# CHIBI_AMP_20181126.net
KiCad netlist of a schematic drawn in Altium Designer
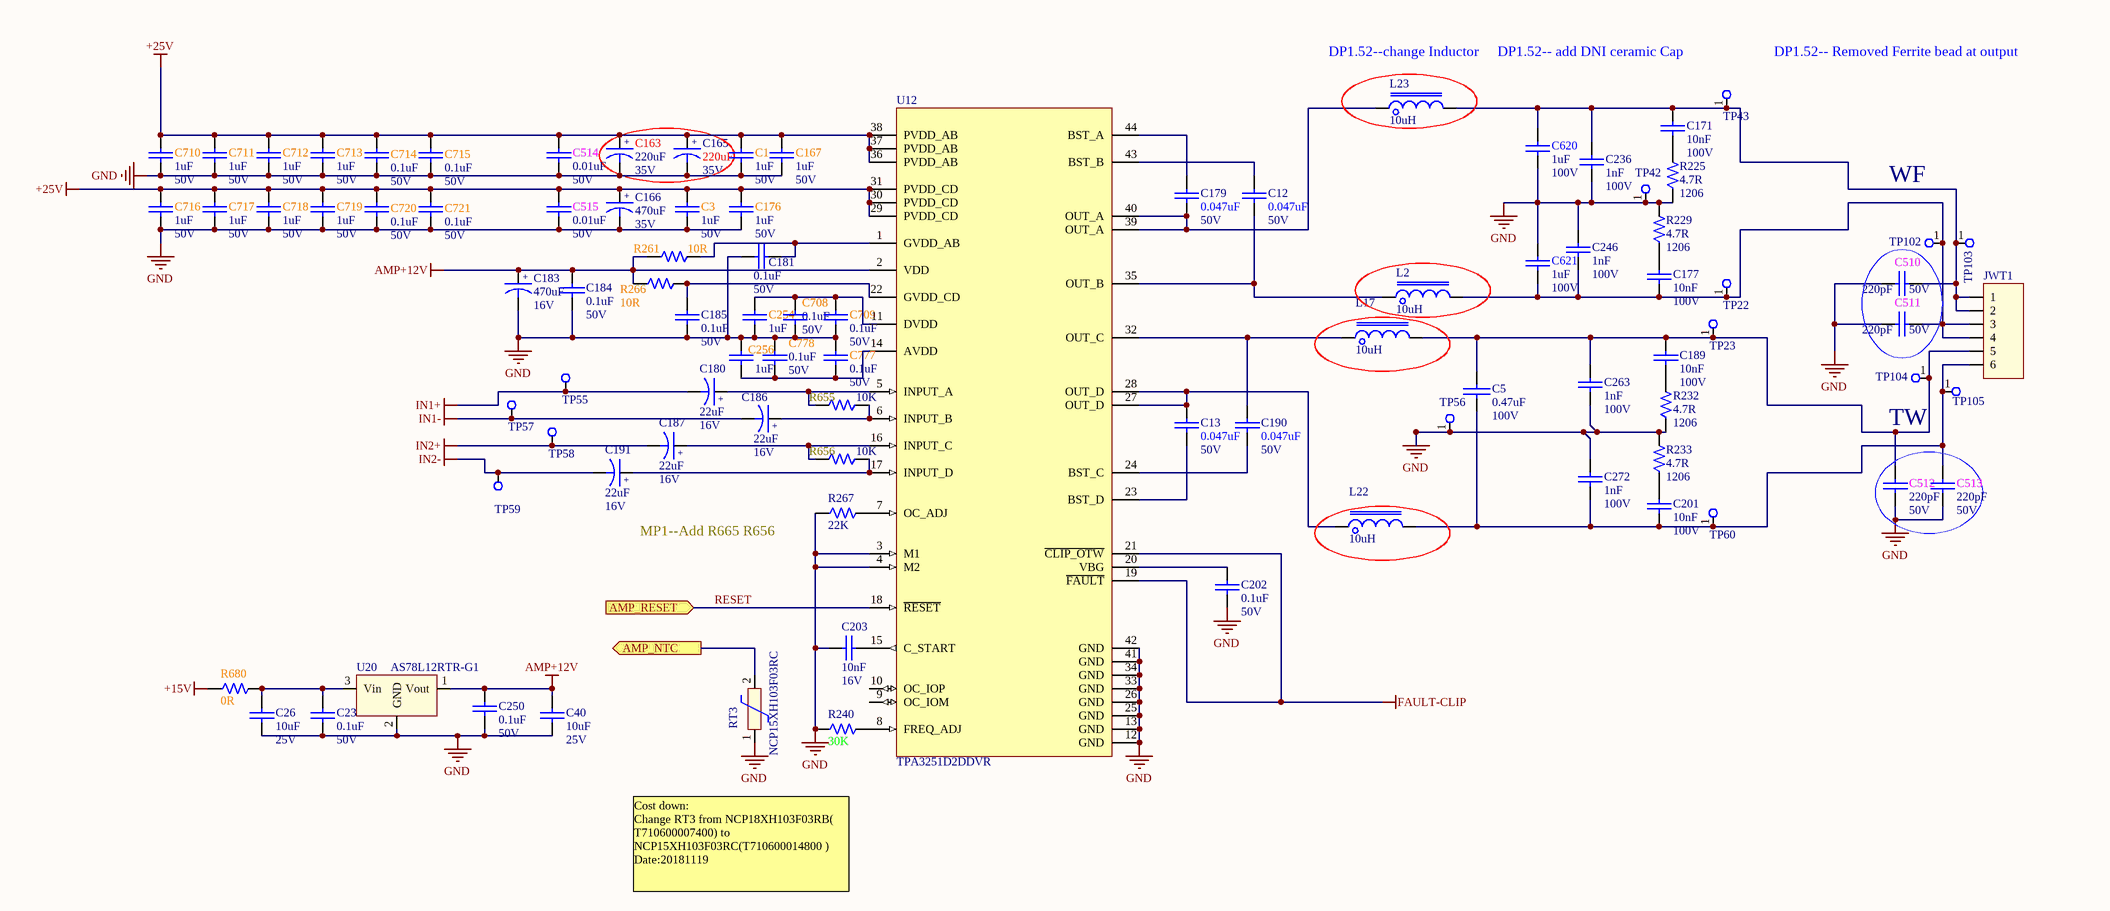
[diagram p0: CHIBI_AMP_20181126.SchDoc]

(export (version "E")
  (design (tool "Eeschema 10.0.6"))
  (components
    (comp (ref "C1")
      (value "1uF")
      (footprint "CAPC0603-RW")
      (description "CAP X7R 1.0UF 50V +-10% 0603 WALSIN L")
      (fields
        (field (name "MFG") "WALSIN")
        (field (name "TOLERANCE") "10%")
        (field (name "VOLTAGE") "50V")
        (field (name "CREATE_NAME") "Nathan")
      )
      (libsource (lib "P-Capacitors") (part "CAP0603 1uF 50V 10%_X7R_WALSIN"))
    )
    (comp (ref "C3")
      (value "1uF")
      (footprint "CAPC0603-RW")
      (description "CAP X7R 1.0UF 50V +-10% 0603 WALSIN L")
      (fields
        (field (name "MFG") "WALSIN")
        (field (name "TOLERANCE") "10%")
        (field (name "VOLTAGE") "50V")
        (field (name "CREATE_NAME") "Nathan")
      )
      (libsource (lib "P-Capacitors") (part "CAP0603 1uF 50V 10%_X7R_WALSIN"))
    )
    (comp (ref "C5")
      (value "0.47uF")
      (footprint "CAP_NP_RADIAL_T4.5W7.5H9.5P5.0")
      (description "COND METAL 0.47uF 100V 5% MINIBOX")
      (fields (field (name "MFG") "佳维诚") (field (name "TOLERANCE") "5%") (field (name "VOLTAGE") "100V"))
      (libsource (lib "P-Capacitors") (part "CAP E METAL 0.47uF 100V 5%"))
    )
    (comp (ref "C12")
      (value "0.047uF")
      (footprint "CAPC0402-RW")
      (description "CAP, CER, 0.047uF, 10%, 50V, X7R, 0402, RoHS")
      (fields
        (field (name "TOLERANCE") "10%")
        (field (name "VOLTAGE") "50V")
        (field (name "Comment") "PWL456470-4730")
        (field (name "CREATE_NAME") "TOM@Deftronics")
      )
      (libsource (lib "P-Capacitors") (part "CAP0402 0.047uF 50V 10%"))
    )
    (comp (ref "C13")
      (value "0.047uF")
      (footprint "CAPC0402-RW")
      (description "CAP, CER, 0.047uF, 10%, 50V, X7R, 0402, RoHS")
      (fields
        (field (name "TOLERANCE") "10%")
        (field (name "VOLTAGE") "50V")
        (field (name "Comment") "PWL456470-4730")
        (field (name "CREATE_NAME") "TOM@Deftronics")
      )
      (libsource (lib "P-Capacitors") (part "CAP0402 0.047uF 50V 10%"))
    )
    (comp (ref "C23")
      (value "0.1uF")
      (footprint "CAPC0603-RW")
      (description "GP CHIP CAP 0.1uF 50V 10% 0603 TYPE X7R")
      (fields
        (field (name "TOLERANCE") "10%")
        (field (name "VOLTAGE") "50V")
        (field (name "Comment") "PXL456470-1040")
      )
      (libsource (lib "P-Capacitors") (part "CAP0603 0.1uF 50V 10% - PXL456470-1040"))
    )
    (comp (ref "C26")
      (value "10uF")
      (footprint "CAPC0805-RW")
      (description "CAP, CER, 10uF, 10%, 25V, X5R, 0805, RoHS")
      (fields
        (field (name "TOLERANCE") "10%")
        (field (name "VOLTAGE") "25V")
        (field (name "Comment") "PYL426450-1060")
        (field (name "CREATE_NAME") "TOM@Deftronics")
      )
      (libsource (lib "P-Capacitors") (part "CAP0805 10uF 25V 10%"))
    )
    (comp (ref "C40")
      (value "10uF")
      (footprint "CAPC0805-RW")
      (description "CAP, CER, 10uF, 10%, 25V, X5R, 0805, RoHS")
      (fields
        (field (name "TOLERANCE") "10%")
        (field (name "VOLTAGE") "25V")
        (field (name "Comment") "PYL426450-1060")
        (field (name "CREATE_NAME") "TOM@Deftronics")
      )
      (libsource (lib "P-Capacitors") (part "CAP0805 10uF 25V 10%"))
    )
    (comp (ref "C163")
      (value "220uF")
      (footprint "CASE - F")
      (description "CHIP ELECT 20% 35V SMD D8xL10.2mm 220uF")
      (fields
        (field (name "TOLERANCE") "20%")
        (field (name "VOLTAGE") "35V")
        (field (name "Comment") "PBE099560-2210")
      )
      (libsource (lib "P-Capacitors") (part "CAP E 220uF 35V 20% SMD"))
    )
    (comp (ref "C165")
      (value "220uF")
      (footprint "CASE - F")
      (description "CHIP ELECT 20% 35V SMD D8xL10.2mm 220uF")
      (fields
        (field (name "TOLERANCE") "20%")
        (field (name "VOLTAGE") "35V")
        (field (name "Comment") "PBE099560-2210")
      )
      (libsource (lib "P-Capacitors") (part "CAP E 220uF 35V 20% SMD"))
    )
    (comp (ref "C166")
      (value "470uF")
      (footprint "CASE - G12.5")
      (description "E 470UF 35V +-20% 10*12. VZH471M1V K")
      (fields
        (field (name "MFG") "LELON")
        (field (name "MFG PART") "VZH471M1V1013-TR0")
        (field (name "VOLTAGE") "35V")
        (field (name "CREAT NAME") "Nathan")
      )
      (libsource (lib "P-Capacitors") (part "CAP E 470uF 35V 20% SMD_VZH471M1V1013-TR0"))
    )
    (comp (ref "C167")
      (value "1uF")
      (footprint "CAPC0603-RW")
      (description "CAP X7R 1.0UF 50V +-10% 0603 WALSIN L")
      (fields
        (field (name "MFG") "WALSIN")
        (field (name "TOLERANCE") "10%")
        (field (name "VOLTAGE") "50V")
        (field (name "CREATE_NAME") "Nathan")
      )
      (libsource (lib "P-Capacitors") (part "CAP0603 1uF 50V 10%_X7R_WALSIN"))
    )
    (comp (ref "C171")
      (value "10nF")
      (footprint "CAPC0805-RW")
      (description "CHIP CAP 10nF 100V 10% 0805 TYPE X7R")
      (fields (field (name "MFG") "Walsin") (field (name "TOLERANCE") "10%") (field (name "VOLTAGE") "100V"))
      (libsource (lib "P-Capacitors") (part "CAP0805 10nF 100V 10%"))
    )
    (comp (ref "C176")
      (value "1uF")
      (footprint "CAPC0603-RW")
      (description "CAP X7R 1.0UF 50V +-10% 0603 WALSIN L")
      (fields
        (field (name "MFG") "WALSIN")
        (field (name "TOLERANCE") "10%")
        (field (name "VOLTAGE") "50V")
        (field (name "CREATE_NAME") "Nathan")
      )
      (libsource (lib "P-Capacitors") (part "CAP0603 1uF 50V 10%_X7R_WALSIN"))
    )
    (comp (ref "C177")
      (value "10nF")
      (footprint "CAPC0805-RW")
      (description "CHIP CAP 10nF 100V 10% 0805 TYPE X7R")
      (fields (field (name "MFG") "Walsin") (field (name "TOLERANCE") "10%") (field (name "VOLTAGE") "100V"))
      (libsource (lib "P-Capacitors") (part "CAP0805 10nF 100V 10%"))
    )
    (comp (ref "C179")
      (value "0.047uF")
      (footprint "CAPC0402-RW")
      (description "CAP, CER, 0.047uF, 10%, 50V, X7R, 0402, RoHS")
      (fields
        (field (name "TOLERANCE") "10%")
        (field (name "VOLTAGE") "50V")
        (field (name "Comment") "PWL456470-4730")
        (field (name "CREATE_NAME") "TOM@Deftronics")
      )
      (libsource (lib "P-Capacitors") (part "CAP0402 0.047uF 50V 10%"))
    )
    (comp (ref "C180")
      (value "22uF")
      (footprint "CASE - B")
      (description "E 22UF 16V +-20% 4X5.4M CK1C220M-CRC54 G")
      (fields
        (field (name "MFG") "NORMAL")
        (field (name "MFG PART") "CK1C220M-CRC54")
        (field (name "VOLTAGE") "16V")
      )
      (libsource (lib "P-Capacitors") (part "CAP E 22uF 16V 20% SMD_CASE-B"))
    )
    (comp (ref "C181")
      (value "0.1uF")
      (footprint "CAPC0603-RW")
      (description "GP CHIP CAP 0.1uF 50V 10% 0603 TYPE X7R")
      (fields
        (field (name "TOLERANCE") "10%")
        (field (name "VOLTAGE") "50V")
        (field (name "Comment") "PXL456470-1040")
      )
      (libsource (lib "P-Capacitors") (part "CAP0603 0.1uF 50V 10% - PXL456470-1040"))
    )
    (comp (ref "C183")
      (value "470uF")
      (footprint "CASE - F")
      (description "CHIP ELECT 20% 16V 150' SMD 470uF 8*10.5mm")
      (fields
        (field (name "MFG") "SEMTECH")
        (field (name "TOLERANCE") "20%")
        (field (name "VOLTAGE") "16V")
        (field (name "CREATE_NAME") "GordonL@Deftronics")
      )
      (libsource (lib "P-Capacitors") (part "CAP E 470u 16V 20% SMD"))
    )
    (comp (ref "C184")
      (value "0.1uF")
      (footprint "CAPC0603-RW")
      (description "GP CHIP CAP 0.1uF 50V 10% 0603 TYPE X7R")
      (fields
        (field (name "TOLERANCE") "10%")
        (field (name "VOLTAGE") "50V")
        (field (name "Comment") "PXL456470-1040")
      )
      (libsource (lib "P-Capacitors") (part "CAP0603 0.1uF 50V 10% - PXL456470-1040"))
    )
    (comp (ref "C185")
      (value "0.1uF")
      (footprint "CAPC0603-RW")
      (description "GP CHIP CAP 0.1uF 50V 10% 0603 TYPE X7R")
      (fields
        (field (name "TOLERANCE") "10%")
        (field (name "VOLTAGE") "50V")
        (field (name "Comment") "PXL456470-1040")
      )
      (libsource (lib "P-Capacitors") (part "CAP0603 0.1uF 50V 10% - PXL456470-1040"))
    )
    (comp (ref "C186")
      (value "22uF")
      (footprint "CASE - B")
      (description "E 22UF 16V +-20% 4X5.4M CK1C220M-CRC54 G")
      (fields
        (field (name "MFG") "NORMAL")
        (field (name "MFG PART") "CK1C220M-CRC54")
        (field (name "VOLTAGE") "16V")
      )
      (libsource (lib "P-Capacitors") (part "CAP E 22uF 16V 20% SMD_CASE-B"))
    )
    (comp (ref "C187")
      (value "22uF")
      (footprint "CASE - B")
      (description "E 22UF 16V +-20% 4X5.4M CK1C220M-CRC54 G")
      (fields
        (field (name "MFG") "NORMAL")
        (field (name "MFG PART") "CK1C220M-CRC54")
        (field (name "VOLTAGE") "16V")
      )
      (libsource (lib "P-Capacitors") (part "CAP E 22uF 16V 20% SMD_CASE-B"))
    )
    (comp (ref "C189")
      (value "10nF")
      (footprint "CAPC0805-RW")
      (description "CHIP CAP 10nF 100V 10% 0805 TYPE X7R")
      (fields (field (name "MFG") "Walsin") (field (name "TOLERANCE") "10%") (field (name "VOLTAGE") "100V"))
      (libsource (lib "P-Capacitors") (part "CAP0805 10nF 100V 10%"))
    )
    (comp (ref "C190")
      (value "0.047uF")
      (footprint "CAPC0402-RW")
      (description "CAP, CER, 0.047uF, 10%, 50V, X7R, 0402, RoHS")
      (fields
        (field (name "TOLERANCE") "10%")
        (field (name "VOLTAGE") "50V")
        (field (name "Comment") "PWL456470-4730")
        (field (name "CREATE_NAME") "TOM@Deftronics")
      )
      (libsource (lib "P-Capacitors") (part "CAP0402 0.047uF 50V 10%"))
    )
    (comp (ref "C191")
      (value "22uF")
      (footprint "CASE - B")
      (description "E 22UF 16V +-20% 4X5.4M CK1C220M-CRC54 G")
      (fields
        (field (name "MFG") "NORMAL")
        (field (name "MFG PART") "CK1C220M-CRC54")
        (field (name "VOLTAGE") "16V")
      )
      (libsource (lib "P-Capacitors") (part "CAP E 22uF 16V 20% SMD_CASE-B"))
    )
    (comp (ref "C201")
      (value "10nF")
      (footprint "CAPC0805-RW")
      (description "CHIP CAP 10nF 100V 10% 0805 TYPE X7R")
      (fields (field (name "MFG") "Walsin") (field (name "TOLERANCE") "10%") (field (name "VOLTAGE") "100V"))
      (libsource (lib "P-Capacitors") (part "CAP0805 10nF 100V 10%"))
    )
    (comp (ref "C202")
      (value "0.1uF")
      (footprint "CAPC0603-RW")
      (description "GP CHIP CAP 0.1uF 50V 10% 0603 TYPE X7R")
      (fields
        (field (name "TOLERANCE") "10%")
        (field (name "VOLTAGE") "50V")
        (field (name "Comment") "PXL456470-1040")
      )
      (libsource (lib "P-Capacitors") (part "CAP0603 0.1uF 50V 10% - PXL456470-1040"))
    )
    (comp (ref "C203")
      (value "10nF")
      (footprint "CAPC0402-RW")
      (description "CHIP CAP 10% 16V 0402 X7R Walsin 10nF")
      (fields
        (field (name "TOLERANCE") "10%")
        (field (name "VOLTAGE") "16V")
        (field (name "Comment") "PWL456440-1030")
      )
      (libsource (lib "P-Capacitors") (part "CAP0402 10nF 16V 10%"))
    )
    (comp (ref "C236")
      (value "1nF")
      (footprint "CAPC0603-RW")
      (description "CHIP CAP 1nF 100V 10%")
      (fields
        (field (name "TOLERANCE") "10%")
        (field (name "VOLTAGE") "100V")
        (field (name "Comment") "PXL4564A2-1020")
      )
      (libsource (lib "P-Capacitors") (part "CAP0603 1nF 100V 10% - PXL4564A2-1020"))
    )
    (comp (ref "C246")
      (value "1nF")
      (footprint "CAPC0603-RW")
      (description "CHIP CAP 1nF 100V 10%")
      (fields
        (field (name "TOLERANCE") "10%")
        (field (name "VOLTAGE") "100V")
        (field (name "Comment") "PXL4564A2-1020")
      )
      (libsource (lib "P-Capacitors") (part "CAP0603 1nF 100V 10% - PXL4564A2-1020"))
    )
    (comp (ref "C250")
      (value "0.1uF")
      (footprint "CAPC0603-RW")
      (description "GP CHIP CAP 0.1uF 50V 10% 0603 TYPE X7R")
      (fields
        (field (name "TOLERANCE") "10%")
        (field (name "VOLTAGE") "50V")
        (field (name "Comment") "PXL456470-1040")
      )
      (libsource (lib "P-Capacitors") (part "CAP0603 0.1uF 50V 10% - PXL456470-1040"))
    )
    (comp (ref "C254")
      (value "1uF")
      (footprint "CAPC0402-RW")
      (description "CAP, CER, 1uF, 5%, 6.3V, X7R, 0402, RoHS")
      (fields
        (field (name "TOLERANCE") "5%")
        (field (name "VOLTAGE") "6.3V")
        (field (name "CREATE_NAME") "TOM@Deftronics")
      )
      (libsource (lib "P-Capacitors") (part "CAP0402 1uF 6.3V 5%"))
    )
    (comp (ref "C256")
      (value "1uF")
      (footprint "CAPC0402-RW")
      (description "CHIP CAP 10% 16V 0402 X7R 1uF")
      (fields (field (name "MFG") "Walsin") (field (name "TOLERANCE") "10%"))
      (libsource (lib "P-Capacitors") (part "CAP0402 1uF 16V 10%"))
    )
    (comp (ref "C263")
      (value "1nF")
      (footprint "CAPC0603-RW")
      (description "CHIP CAP 1nF 100V 10%")
      (fields
        (field (name "TOLERANCE") "10%")
        (field (name "VOLTAGE") "100V")
        (field (name "Comment") "PXL4564A2-1020")
      )
      (libsource (lib "P-Capacitors") (part "CAP0603 1nF 100V 10% - PXL4564A2-1020"))
    )
    (comp (ref "C272")
      (value "1nF")
      (footprint "CAPC0603-RW")
      (description "CHIP CAP 1nF 100V 10%")
      (fields
        (field (name "TOLERANCE") "10%")
        (field (name "VOLTAGE") "100V")
        (field (name "Comment") "PXL4564A2-1020")
      )
      (libsource (lib "P-Capacitors") (part "CAP0603 1nF 100V 10% - PXL4564A2-1020"))
    )
    (comp (ref "C510")
      (value "220pF")
      (footprint "CAPC0402-RW")
      (description "CHIP CAP 220pF 50V 5% 0402 TYPE NPO")
      (fields (field (name "MFG") "Walsin") (field (name "TOLERANCE") "5%") (field (name "VOLTAGE") "50V"))
      (libsource (lib "P-Capacitors") (part "CAP0402 220pF 50V 5%"))
    )
    (comp (ref "C511")
      (value "220pF")
      (footprint "CAPC0402-RW")
      (description "CHIP CAP 220pF 50V 5% 0402 TYPE NPO")
      (fields (field (name "MFG") "Walsin") (field (name "TOLERANCE") "5%") (field (name "VOLTAGE") "50V"))
      (libsource (lib "P-Capacitors") (part "CAP0402 220pF 50V 5%"))
    )
    (comp (ref "C512")
      (value "220pF")
      (footprint "CAPC0402-RW")
      (description "CHIP CAP 220pF 50V 5% 0402 TYPE NPO")
      (fields (field (name "MFG") "Walsin") (field (name "TOLERANCE") "5%") (field (name "VOLTAGE") "50V"))
      (libsource (lib "P-Capacitors") (part "CAP0402 220pF 50V 5%"))
    )
    (comp (ref "C513")
      (value "220pF")
      (footprint "CAPC0402-RW")
      (description "CHIP CAP 220pF 50V 5% 0402 TYPE NPO")
      (fields (field (name "MFG") "Walsin") (field (name "TOLERANCE") "5%") (field (name "VOLTAGE") "50V"))
      (libsource (lib "P-Capacitors") (part "CAP0402 220pF 50V 5%"))
    )
    (comp (ref "C514")
      (value "0.01uF")
      (footprint "CAPC0402-RW")
      (description "CAP, CER, 0.01uF, 10%, 50V, X7R, 0402, RoHS")
      (fields
        (field (name "TOLERANCE") "10%")
        (field (name "VOLTAGE") "50V")
        (field (name "Comment") "PWL456470-1030")
        (field (name "CREATE_NAME") "Evan@Deftronics")
      )
      (libsource (lib "P-Capacitors") (part "CAP0402 0.01uF 50V 10%"))
    )
    (comp (ref "C515")
      (value "0.01uF")
      (footprint "CAPC0402-RW")
      (description "CAP, CER, 0.01uF, 10%, 50V, X7R, 0402, RoHS")
      (fields
        (field (name "TOLERANCE") "10%")
        (field (name "VOLTAGE") "50V")
        (field (name "Comment") "PWL456470-1030")
        (field (name "CREATE_NAME") "Evan@Deftronics")
      )
      (libsource (lib "P-Capacitors") (part "CAP0402 0.01uF 50V 10%"))
    )
    (comp (ref "C620")
      (value "1uF")
      (footprint "CAPC0805-RW")
      (description "CAP 1.0UF 100V +-10% 0805X7S TDK L")
      (fields
        (field (name "MFG") "TDK")
        (field (name "TOLERANCE") "10%")
        (field (name "VOLTAGE") "100V")
        (field (name "CREATE_NAME") "Nathan")
      )
      (libsource (lib "P-Capacitors") (part "CAPC0805 1uF 100V 10%_X7S_TDK"))
    )
    (comp (ref "C621")
      (value "1uF")
      (footprint "CAPC0805-RW")
      (description "CAP 1.0UF 100V +-10% 0805X7S TDK L")
      (fields
        (field (name "MFG") "TDK")
        (field (name "TOLERANCE") "10%")
        (field (name "VOLTAGE") "100V")
        (field (name "CREATE_NAME") "Nathan")
      )
      (libsource (lib "P-Capacitors") (part "CAPC0805 1uF 100V 10%_X7S_TDK"))
    )
    (comp (ref "C708")
      (value "0.1uF")
      (footprint "CAPC0402-RW")
      (description "CAP, CER, 0.1uF, 10%, 50V, X7R, 0402, RoHS")
      (fields
        (field (name "TOLERANCE") "10%")
        (field (name "VOLTAGE") "50V")
        (field (name "Comment") "PWL456470-1040")
        (field (name "CREATE_NAME") "TOM@Deftronics")
      )
      (libsource (lib "P-Capacitors") (part "CAP0402 0.1uF 50V 10%"))
    )
    (comp (ref "C709")
      (value "0.1uF")
      (footprint "CAPC0402-RW")
      (description "CAP, CER, 0.1uF, 10%, 50V, X7R, 0402, RoHS")
      (fields
        (field (name "TOLERANCE") "10%")
        (field (name "VOLTAGE") "50V")
        (field (name "Comment") "PWL456470-1040")
        (field (name "CREATE_NAME") "TOM@Deftronics")
      )
      (libsource (lib "P-Capacitors") (part "CAP0402 0.1uF 50V 10%"))
    )
    (comp (ref "C710")
      (value "1uF")
      (footprint "CAPC0603-RW")
      (description "CAP X7R 1.0UF 50V +-10% 0603 WALSIN L")
      (fields
        (field (name "MFG") "WALSIN")
        (field (name "TOLERANCE") "10%")
        (field (name "VOLTAGE") "50V")
        (field (name "CREATE_NAME") "Nathan")
      )
      (libsource (lib "P-Capacitors") (part "CAP0603 1uF 50V 10%_X7R_WALSIN"))
    )
    (comp (ref "C711")
      (value "1uF")
      (footprint "CAPC0603-RW")
      (description "CAP X7R 1.0UF 50V +-10% 0603 WALSIN L")
      (fields
        (field (name "MFG") "WALSIN")
        (field (name "TOLERANCE") "10%")
        (field (name "VOLTAGE") "50V")
        (field (name "CREATE_NAME") "Nathan")
      )
      (libsource (lib "P-Capacitors") (part "CAP0603 1uF 50V 10%_X7R_WALSIN"))
    )
    (comp (ref "C712")
      (value "1uF")
      (footprint "CAPC0603-RW")
      (description "CAP X7R 1.0UF 50V +-10% 0603 WALSIN L")
      (fields
        (field (name "MFG") "WALSIN")
        (field (name "TOLERANCE") "10%")
        (field (name "VOLTAGE") "50V")
        (field (name "CREATE_NAME") "Nathan")
      )
      (libsource (lib "P-Capacitors") (part "CAP0603 1uF 50V 10%_X7R_WALSIN"))
    )
    (comp (ref "C713")
      (value "1uF")
      (footprint "CAPC0603-RW")
      (description "CAP X7R 1.0UF 50V +-10% 0603 WALSIN L")
      (fields
        (field (name "MFG") "WALSIN")
        (field (name "TOLERANCE") "10%")
        (field (name "VOLTAGE") "50V")
        (field (name "CREATE_NAME") "Nathan")
      )
      (libsource (lib "P-Capacitors") (part "CAP0603 1uF 50V 10%_X7R_WALSIN"))
    )
    (comp (ref "C714")
      (value "0.1uF")
      (footprint "CAPC0402-RW")
      (description "CAP, CER, 0.1uF, 10%, 50V, X7R, 0402, RoHS")
      (fields
        (field (name "TOLERANCE") "10%")
        (field (name "VOLTAGE") "50V")
        (field (name "Comment") "PWL456470-1040")
        (field (name "CREATE_NAME") "TOM@Deftronics")
      )
      (libsource (lib "P-Capacitors") (part "CAP0402 0.1uF 50V 10%"))
    )
    (comp (ref "C715")
      (value "0.1uF")
      (footprint "CAPC0402-RW")
      (description "CAP, CER, 0.1uF, 10%, 50V, X7R, 0402, RoHS")
      (fields
        (field (name "TOLERANCE") "10%")
        (field (name "VOLTAGE") "50V")
        (field (name "Comment") "PWL456470-1040")
        (field (name "CREATE_NAME") "TOM@Deftronics")
      )
      (libsource (lib "P-Capacitors") (part "CAP0402 0.1uF 50V 10%"))
    )
    (comp (ref "C716")
      (value "1uF")
      (footprint "CAPC0603-RW")
      (description "CAP X7R 1.0UF 50V +-10% 0603 WALSIN L")
      (fields
        (field (name "MFG") "WALSIN")
        (field (name "TOLERANCE") "10%")
        (field (name "VOLTAGE") "50V")
        (field (name "CREATE_NAME") "Nathan")
      )
      (libsource (lib "P-Capacitors") (part "CAP0603 1uF 50V 10%_X7R_WALSIN"))
    )
    (comp (ref "C717")
      (value "1uF")
      (footprint "CAPC0603-RW")
      (description "CAP X7R 1.0UF 50V +-10% 0603 WALSIN L")
      (fields
        (field (name "MFG") "WALSIN")
        (field (name "TOLERANCE") "10%")
        (field (name "VOLTAGE") "50V")
        (field (name "CREATE_NAME") "Nathan")
      )
      (libsource (lib "P-Capacitors") (part "CAP0603 1uF 50V 10%_X7R_WALSIN"))
    )
    (comp (ref "C718")
      (value "1uF")
      (footprint "CAPC0603-RW")
      (description "CAP X7R 1.0UF 50V +-10% 0603 WALSIN L")
      (fields
        (field (name "MFG") "WALSIN")
        (field (name "TOLERANCE") "10%")
        (field (name "VOLTAGE") "50V")
        (field (name "CREATE_NAME") "Nathan")
      )
      (libsource (lib "P-Capacitors") (part "CAP0603 1uF 50V 10%_X7R_WALSIN"))
    )
    (comp (ref "C719")
      (value "1uF")
      (footprint "CAPC0603-RW")
      (description "CAP X7R 1.0UF 50V +-10% 0603 WALSIN L")
      (fields
        (field (name "MFG") "WALSIN")
        (field (name "TOLERANCE") "10%")
        (field (name "VOLTAGE") "50V")
        (field (name "CREATE_NAME") "Nathan")
      )
      (libsource (lib "P-Capacitors") (part "CAP0603 1uF 50V 10%_X7R_WALSIN"))
    )
    (comp (ref "C720")
      (value "0.1uF")
      (footprint "CAPC0402-RW")
      (description "CAP, CER, 0.1uF, 10%, 50V, X7R, 0402, RoHS")
      (fields
        (field (name "TOLERANCE") "10%")
        (field (name "VOLTAGE") "50V")
        (field (name "Comment") "PWL456470-1040")
        (field (name "CREATE_NAME") "TOM@Deftronics")
      )
      (libsource (lib "P-Capacitors") (part "CAP0402 0.1uF 50V 10%"))
    )
    (comp (ref "C721")
      (value "0.1uF")
      (footprint "CAPC0402-RW")
      (description "CAP, CER, 0.1uF, 10%, 50V, X7R, 0402, RoHS")
      (fields
        (field (name "TOLERANCE") "10%")
        (field (name "VOLTAGE") "50V")
        (field (name "Comment") "PWL456470-1040")
        (field (name "CREATE_NAME") "TOM@Deftronics")
      )
      (libsource (lib "P-Capacitors") (part "CAP0402 0.1uF 50V 10%"))
    )
    (comp (ref "C777")
      (value "0.1uF")
      (footprint "CAPC0402-RW")
      (description "CAP, CER, 0.1uF, 10%, 50V, X7R, 0402, RoHS")
      (fields
        (field (name "TOLERANCE") "10%")
        (field (name "VOLTAGE") "50V")
        (field (name "Comment") "PWL456470-1040")
        (field (name "CREATE_NAME") "TOM@Deftronics")
      )
      (libsource (lib "P-Capacitors") (part "CAP0402 0.1uF 50V 10%"))
    )
    (comp (ref "C778")
      (value "0.1uF")
      (footprint "CAPC0402-RW")
      (description "CAP, CER, 0.1uF, 10%, 50V, X7R, 0402, RoHS")
      (fields
        (field (name "TOLERANCE") "10%")
        (field (name "VOLTAGE") "50V")
        (field (name "Comment") "PWL456470-1040")
        (field (name "CREATE_NAME") "TOM@Deftronics")
      )
      (libsource (lib "P-Capacitors") (part "CAP0402 0.1uF 50V 10%"))
    )
    (comp (ref "JWT1")
      (value "T690300097400")
      (footprint "CONN 6P PH=2.5MM ST")
      (description "CONNECTOR TJC3-6A-CS 6 PIN G")
      (fields
        (field (name "MFG") "金佳电子")
        (field (name "MFG PART") "TJC3-6A-CS")
        (field (name "CREATE_NAME") "Tom")
      )
      (libsource (lib "C-Connector") (part "CONN 6P PH=2.5MM ST"))
    )
    (comp (ref "L2")
      (value "10uH")
      (footprint "IND_CKCH129")
      (description "10UH 10A 100K 12.3 CENKER CKCH129 K")
      (fields
        (field (name "MFG") "CENKER")
        (field (name "MFG PART") "CKCH129-10U~{H}M")
        (field (name "CREATE_NAME") "Nathan")
      )
      (libsource (lib "S-Inductor") (part "IND 10uH CKCH129-10UH{backslash}M"))
    )
    (comp (ref "L17")
      (value "10uH")
      (footprint "IND_CKCH88")
      (description "10UH 6A 100K 8.0X CENKER CKCH88- K")
      (fields
        (field (name "MFG") "CENKER")
        (field (name "MFG PART") "CKCH88-10U~{H}M")
        (field (name "CREATE_NAME") "Nathan")
      )
      (libsource (lib "S-Inductor") (part "IND 10uH CKCH88-10UH{backslash}M"))
    )
    (comp (ref "L22")
      (value "10uH")
      (footprint "IND_CKCH88")
      (description "10UH 6A 100K 8.0X CENKER CKCH88- K")
      (fields
        (field (name "MFG") "CENKER")
        (field (name "MFG PART") "CKCH88-10U~{H}M")
        (field (name "CREATE_NAME") "Nathan")
      )
      (libsource (lib "S-Inductor") (part "IND 10uH CKCH88-10UH{backslash}M"))
    )
    (comp (ref "L23")
      (value "10uH")
      (footprint "IND_CKCH129")
      (description "10UH 10A 100K 12.3 CENKER CKCH129 K")
      (fields
        (field (name "MFG") "CENKER")
        (field (name "MFG PART") "CKCH129-10U~{H}M")
        (field (name "CREATE_NAME") "Nathan")
      )
      (libsource (lib "S-Inductor") (part "IND 10uH CKCH129-10UH{backslash}M"))
    )
    (comp (ref "R225")
      (value "4.7R")
      (footprint "1206-RW")
      (description "CHIP RES 4.7 OHM 1/4 W 1% 1206")
      (fields (field (name "PACKAGE") "1206") (field (name "Comment") "QCF041010-4708"))
      (libsource (lib "Q-Resistors") (part "RES1206 1/4W 1% 4.7 OHM"))
    )
    (comp (ref "R229")
      (value "4.7R")
      (footprint "1206-RW")
      (description "CHIP RES 4.7 OHM 1/4 W 1% 1206")
      (fields (field (name "PACKAGE") "1206") (field (name "Comment") "QCF041010-4708"))
      (libsource (lib "Q-Resistors") (part "RES1206 1/4W 1% 4.7 OHM"))
    )
    (comp (ref "R232")
      (value "4.7R")
      (footprint "1206-RW")
      (description "CHIP RES 4.7 OHM 1/4 W 1% 1206")
      (fields (field (name "PACKAGE") "1206") (field (name "Comment") "QCF041010-4708"))
      (libsource (lib "Q-Resistors") (part "RES1206 1/4W 1% 4.7 OHM"))
    )
    (comp (ref "R233")
      (value "4.7R")
      (footprint "1206-RW")
      (description "CHIP RES 4.7 OHM 1/4 W 1% 1206")
      (fields (field (name "PACKAGE") "1206") (field (name "Comment") "QCF041010-4708"))
      (libsource (lib "Q-Resistors") (part "RES1206 1/4W 1% 4.7 OHM"))
    )
    (comp (ref "R240")
      (value "30K")
      (footprint "0402-RW")
      (description "CHIP RES  30K OHM 1/16W 1% 0402")
      (fields (field (name "Comment") "QCF161240-3002") (field (name "CREATE_NAME") "GordonL@Deftronics"))
      (libsource (lib "Q-Resistors") (part "RES0402 1/16W 1% 30K OHM"))
    )
    (comp (ref "R261")
      (value "10R")
      (footprint "0603-RW")
      (description "GP CHIP RES. 10 OHM 1/10W 1% 0603")
      (fields (field (name "Comment") "QCF011030-1009"))
      (libsource (lib "Q-Resistors") (part "RES0603 1/10W 1% 10 OHM"))
    )
    (comp (ref "R266")
      (value "10R")
      (footprint "0603-RW")
      (description "GP CHIP RES. 10 OHM 1/10W 1% 0603")
      (fields (field (name "Comment") "QCF011030-1009"))
      (libsource (lib "Q-Resistors") (part "RES0603 1/10W 1% 10 OHM"))
    )
    (comp (ref "R267")
      (value "22K")
      (footprint "0402-RW")
      (description "CHIP RES 22K OHM 1/16W 1% 0402")
      (fields (field (name "MFG") "WALSIN") (field (name "Comment") "QCF161240-2202"))
      (libsource (lib "Q-Resistors") (part "RES0402 1/16W 1% 22K OHM"))
    )
    (comp (ref "R655")
      (value "10K")
      (footprint "0402-RW")
      (description "CHIP RES 10K OHM 1/16W 1% 0402")
      (fields (field (name "MFG") "WALSIN") (field (name "Comment") "QCF161240-1002"))
      (libsource (lib "Q-Resistors") (part "RES0402 1/16W 1% 10K OHM"))
    )
    (comp (ref "R656")
      (value "10K")
      (footprint "0402-RW")
      (description "CHIP RES 10K OHM 1/16W 1% 0402")
      (fields (field (name "MFG") "WALSIN") (field (name "Comment") "QCF161240-1002"))
      (libsource (lib "Q-Resistors") (part "RES0402 1/16W 1% 10K OHM"))
    )
    (comp (ref "R680")
      (value "0R")
      (footprint "0603-RW")
      (description "CHIP 0 OHM 0 OHM 0 OHM 0603 WALSIN L")
      (fields (field (name "MFG PART") "WR06X000PTL") (field (name "MFG") "WALSIN (華新)"))
      (libsource (lib "Q-Resistors") (part "RES0603 1/10W 0 OHM_WALSIN"))
    )
    (comp (ref "RT3")
      (value "NTC NCP15XH103F03RC")
      (footprint "0402-RW")
      (description "NTC Thermistor NCP15XH103F03RC")
      (fields
        (field (name "MFG") "muRata")
        (field (name "MFG PART") "NCP15XH103F03RC")
        (field (name "CREATE_NAME") "Nathan")
      )
      (libsource (lib "Temporary") (part "NTC NCP15XH103F03RC"))
    )
    (comp (ref "TP22") (value "TP") (footprint "TP_2.0mm") (libsource (lib "Temporary") (part "TP")))
    (comp (ref "TP23") (value "TP") (footprint "TP_2.0mm") (libsource (lib "Temporary") (part "TP")))
    (comp (ref "TP42") (value "TP") (footprint "TP_1.8mm") (libsource (lib "Temporary") (part "TP")))
    (comp (ref "TP43") (value "TP") (footprint "TP_2.0mm") (libsource (lib "Temporary") (part "TP")))
    (comp (ref "TP55") (value "TP") (footprint "TP_1.2mm") (libsource (lib "") (part "TP_1")))
    (comp (ref "TP56") (value "TP") (footprint "TP_1.8mm") (libsource (lib "Temporary") (part "TP")))
    (comp (ref "TP57") (value "TP") (footprint "TP_1.2mm") (libsource (lib "") (part "TP_1")))
    (comp (ref "TP58") (value "TP") (footprint "TP_1.2mm") (libsource (lib "") (part "TP_1")))
    (comp (ref "TP59") (value "TP") (footprint "TP_1.2mm") (libsource (lib "") (part "TP_1")))
    (comp (ref "TP60") (value "TP") (footprint "TP_2.0mm") (libsource (lib "Temporary") (part "TP")))
    (comp (ref "TP102")
      (value "D1.2V")
      (footprint "TP_1.2mm")
      (description "TP")
      (libsource (lib "Temporary") (part "TP"))
    )
    (comp (ref "TP103")
      (value "D1.2V")
      (footprint "TP_1.2mm")
      (description "TP")
      (libsource (lib "Temporary") (part "TP"))
    )
    (comp (ref "TP104")
      (value "D1.2V")
      (footprint "TP_1.2mm")
      (description "TP")
      (libsource (lib "Temporary") (part "TP"))
    )
    (comp (ref "TP105")
      (value "D1.2V")
      (footprint "TP_1.2mm")
      (description "TP")
      (libsource (lib "Temporary") (part "TP"))
    )
    (comp (ref "U12")
      (value "T610500031401")
      (footprint "DDV(R-PDSO-G44)")
      (description "OP TPA3251D2DDVR HTSSOP-4 TI G")
      (fields
        (field (name "MFG") "TI")
        (field (name "MFG PART") "TPA3251D2DDVR")
        (field (name "CREATE_NAME") "Tom")
      )
      (libsource (lib "R-Semiconductors") (part "TPA3251D2DDVR"))
    )
    (comp (ref "U20")
      (value "T610600095367")
      (footprint "SOT89")
      (description "REG AS78L12RTR-G1 SOT-89 DIODES G")
      (fields
        (field (name "MFG") "DIODES INCORPORATED (BCD)")
        (field (name "MFG PART") "AS78L12RTR-G1")
        (field (name "CREAT_NAME") "Nathan")
      )
      (libsource (lib "R-Semiconductors") (part "AS78L12RTR-G1"))
    )
  )
  (nets
    (net (code "1") (name "+15V") (class "Default")
      (node (ref "R680") (pin "1") (pinfunction "1_1") (pintype "passive"))
    )
    (net (code "2") (name "+25V") (class "Default")
      (node (ref "C1") (pin "1") (pinfunction "1_1") (pintype "passive"))
      (node (ref "C163") (pin "1") (pinfunction "1_1") (pintype "passive"))
      (node (ref "C165") (pin "1") (pinfunction "1_1") (pintype "passive"))
      (node (ref "C166") (pin "1") (pinfunction "1_1") (pintype "passive"))
      (node (ref "C167") (pin "1") (pinfunction "1_1") (pintype "passive"))
      (node (ref "C176") (pin "1") (pinfunction "1_1") (pintype "passive"))
      (node (ref "C3") (pin "1") (pinfunction "1_1") (pintype "passive"))
      (node (ref "C514") (pin "1") (pinfunction "1_1") (pintype "passive"))
      (node (ref "C515") (pin "1") (pinfunction "1_1") (pintype "passive"))
      (node (ref "C710") (pin "1") (pinfunction "1_1") (pintype "passive"))
      (node (ref "C711") (pin "1") (pinfunction "1_1") (pintype "passive"))
      (node (ref "C712") (pin "1") (pinfunction "1_1") (pintype "passive"))
      (node (ref "C713") (pin "1") (pinfunction "1_1") (pintype "passive"))
      (node (ref "C714") (pin "2") (pinfunction "2_2") (pintype "passive"))
      (node (ref "C715") (pin "2") (pinfunction "2_2") (pintype "passive"))
      (node (ref "C716") (pin "1") (pinfunction "1_1") (pintype "passive"))
      (node (ref "C717") (pin "1") (pinfunction "1_1") (pintype "passive"))
      (node (ref "C718") (pin "1") (pinfunction "1_1") (pintype "passive"))
      (node (ref "C719") (pin "1") (pinfunction "1_1") (pintype "passive"))
      (node (ref "C720") (pin "2") (pinfunction "2_2") (pintype "passive"))
      (node (ref "C721") (pin "2") (pinfunction "2_2") (pintype "passive"))
      (node (ref "U12") (pin "29") (pinfunction "PVDD_CD_29") (pintype "power_in"))
      (node (ref "U12") (pin "30") (pinfunction "PVDD_CD_30") (pintype "power_in"))
      (node (ref "U12") (pin "31") (pinfunction "PVDD_CD_31") (pintype "power_in"))
      (node (ref "U12") (pin "36") (pinfunction "PVDD_AB_36") (pintype "power_in"))
      (node (ref "U12") (pin "37") (pinfunction "PVDD_AB_37") (pintype "power_in"))
      (node (ref "U12") (pin "38") (pinfunction "PVDD_AB_38") (pintype "power_in"))
    )
    (net (code "3") (name "/AMP_NTC") (class "Default")
      (node (ref "RT3") (pin "2") (pinfunction "2_2") (pintype "passive"))
    )
    (net (code "4") (name "/RESET") (class "Default")
      (node (ref "U12") (pin "18") (pinfunction "~{RESET}_18") (pintype "input"))
    )
    (net (code "5") (name "AMP+12V") (class "Default")
      (node (ref "C183") (pin "1") (pinfunction "1_1") (pintype "passive"))
      (node (ref "C184") (pin "1") (pinfunction "1_1") (pintype "passive"))
      (node (ref "C250") (pin "2") (pinfunction "2_2") (pintype "passive"))
      (node (ref "C40") (pin "1") (pinfunction "1_1") (pintype "passive"))
      (node (ref "R261") (pin "1") (pinfunction "1_1") (pintype "passive"))
      (node (ref "R266") (pin "1") (pinfunction "1_1") (pintype "passive"))
      (node (ref "U12") (pin "2") (pinfunction "VDD_2") (pintype "power_in"))
      (node (ref "U20") (pin "1") (pinfunction "Vout_1") (pintype "passive"))
    )
    (net (code "6") (name "FAULT-CLIP") (class "Default")
      (node (ref "U12") (pin "19") (pinfunction "~{FAULT}_19") (pintype "open_collector"))
      (node (ref "U12") (pin "21") (pinfunction "~{CLIP_OTW}_21") (pintype "open_collector"))
    )
    (net (code "7") (name "GND") (class "Default")
      (node (ref "C1") (pin "2") (pinfunction "2_2") (pintype "passive"))
      (node (ref "C163") (pin "2") (pinfunction "2_2") (pintype "passive"))
      (node (ref "C165") (pin "2") (pinfunction "2_2") (pintype "passive"))
      (node (ref "C166") (pin "2") (pinfunction "2_2") (pintype "passive"))
      (node (ref "C167") (pin "2") (pinfunction "2_2") (pintype "passive"))
      (node (ref "C176") (pin "2") (pinfunction "2_2") (pintype "passive"))
      (node (ref "C181") (pin "1") (pinfunction "1_1") (pintype "passive"))
      (node (ref "C183") (pin "2") (pinfunction "2_2") (pintype "passive"))
      (node (ref "C184") (pin "2") (pinfunction "2_2") (pintype "passive"))
      (node (ref "C185") (pin "1") (pinfunction "1_1") (pintype "passive"))
      (node (ref "C202") (pin "2") (pinfunction "2_2") (pintype "passive"))
      (node (ref "C203") (pin "1") (pinfunction "1_1") (pintype "passive"))
      (node (ref "C23") (pin "2") (pinfunction "2_2") (pintype "passive"))
      (node (ref "C236") (pin "2") (pinfunction "2_2") (pintype "passive"))
      (node (ref "C246") (pin "1") (pinfunction "1_1") (pintype "passive"))
      (node (ref "C250") (pin "1") (pinfunction "1_1") (pintype "passive"))
      (node (ref "C254") (pin "1") (pinfunction "1_1") (pintype "passive"))
      (node (ref "C256") (pin "1") (pinfunction "1_1") (pintype "passive"))
      (node (ref "C26") (pin "2") (pinfunction "2_2") (pintype "passive"))
      (node (ref "C263") (pin "2") (pinfunction "2_2") (pintype "passive"))
      (node (ref "C272") (pin "1") (pinfunction "1_1") (pintype "passive"))
      (node (ref "C3") (pin "2") (pinfunction "2_2") (pintype "passive"))
      (node (ref "C40") (pin "2") (pinfunction "2_2") (pintype "passive"))
      (node (ref "C510") (pin "2") (pinfunction "2_2") (pintype "passive"))
      (node (ref "C511") (pin "2") (pinfunction "2_2") (pintype "passive"))
      (node (ref "C512") (pin "2") (pinfunction "2_2") (pintype "passive"))
      (node (ref "C513") (pin "2") (pinfunction "2_2") (pintype "passive"))
      (node (ref "C514") (pin "2") (pinfunction "2_2") (pintype "passive"))
      (node (ref "C515") (pin "2") (pinfunction "2_2") (pintype "passive"))
      (node (ref "C620") (pin "2") (pinfunction "2_2") (pintype "passive"))
      (node (ref "C621") (pin "1") (pinfunction "1_1") (pintype "passive"))
      (node (ref "C708") (pin "2") (pinfunction "2_2") (pintype "passive"))
      (node (ref "C709") (pin "2") (pinfunction "2_2") (pintype "passive"))
      (node (ref "C710") (pin "2") (pinfunction "2_2") (pintype "passive"))
      (node (ref "C711") (pin "2") (pinfunction "2_2") (pintype "passive"))
      (node (ref "C712") (pin "2") (pinfunction "2_2") (pintype "passive"))
      (node (ref "C713") (pin "2") (pinfunction "2_2") (pintype "passive"))
      (node (ref "C714") (pin "1") (pinfunction "1_1") (pintype "passive"))
      (node (ref "C715") (pin "1") (pinfunction "1_1") (pintype "passive"))
      (node (ref "C716") (pin "2") (pinfunction "2_2") (pintype "passive"))
      (node (ref "C717") (pin "2") (pinfunction "2_2") (pintype "passive"))
      (node (ref "C718") (pin "2") (pinfunction "2_2") (pintype "passive"))
      (node (ref "C719") (pin "2") (pinfunction "2_2") (pintype "passive"))
      (node (ref "C720") (pin "1") (pinfunction "1_1") (pintype "passive"))
      (node (ref "C721") (pin "1") (pinfunction "1_1") (pintype "passive"))
      (node (ref "C777") (pin "1") (pinfunction "1_1") (pintype "passive"))
      (node (ref "C778") (pin "1") (pinfunction "1_1") (pintype "passive"))
      (node (ref "R225") (pin "1") (pinfunction "1_1") (pintype "passive"))
      (node (ref "R229") (pin "2") (pinfunction "2_2") (pintype "passive"))
      (node (ref "R232") (pin "1") (pinfunction "1_1") (pintype "passive"))
      (node (ref "R233") (pin "2") (pinfunction "2_2") (pintype "passive"))
      (node (ref "R240") (pin "1") (pinfunction "1_1") (pintype "passive"))
      (node (ref "R267") (pin "1") (pinfunction "1_1") (pintype "passive"))
      (node (ref "RT3") (pin "1") (pinfunction "1_1") (pintype "passive"))
      (node (ref "TP42") (pin "1") (pinfunction "1_1") (pintype "passive"))
      (node (ref "TP56") (pin "1") (pinfunction "1_1") (pintype "passive"))
      (node (ref "U12") (pin "12") (pinfunction "GND_12") (pintype "power_in"))
      (node (ref "U12") (pin "13") (pinfunction "GND_13") (pintype "power_in"))
      (node (ref "U12") (pin "25") (pinfunction "GND_25") (pintype "power_in"))
      (node (ref "U12") (pin "26") (pinfunction "GND_26") (pintype "power_in"))
      (node (ref "U12") (pin "3") (pinfunction "M1_3") (pintype "input"))
      (node (ref "U12") (pin "33") (pinfunction "GND_33") (pintype "power_in"))
      (node (ref "U12") (pin "34") (pinfunction "GND_34") (pintype "power_in"))
      (node (ref "U12") (pin "4") (pinfunction "M2_4") (pintype "input"))
      (node (ref "U12") (pin "41") (pinfunction "GND_41") (pintype "power_in"))
      (node (ref "U12") (pin "42") (pinfunction "GND_42") (pintype "power_in"))
      (node (ref "U20") (pin "2") (pinfunction "GND_2") (pintype "passive"))
    )
    (net (code "8") (name "IN1+") (class "Default")
      (node (ref "C180") (pin "2") (pinfunction "2_2") (pintype "passive"))
      (node (ref "TP55") (pin "1") (pinfunction "1_1") (pintype "passive"))
    )
    (net (code "9") (name "IN1-") (class "Default")
      (node (ref "C186") (pin "2") (pinfunction "2_2") (pintype "passive"))
      (node (ref "TP57") (pin "1") (pinfunction "1_1") (pintype "passive"))
    )
    (net (code "10") (name "IN2+") (class "Default")
      (node (ref "C187") (pin "2") (pinfunction "2_2") (pintype "passive"))
      (node (ref "TP58") (pin "1") (pinfunction "1_1") (pintype "passive"))
    )
    (net (code "11") (name "IN2-") (class "Default")
      (node (ref "C191") (pin "2") (pinfunction "2_2") (pintype "passive"))
      (node (ref "TP59") (pin "1") (pinfunction "1_1") (pintype "passive"))
    )
    (net (code "12") (name "Net-(C13-Pad1)") (class "Default")
      (node (ref "C13") (pin "1") (pinfunction "1_1") (pintype "passive"))
      (node (ref "L22") (pin "1") (pinfunction "1_1") (pintype "passive"))
      (node (ref "U12") (pin "27") (pinfunction "OUT_D_27") (pintype "power_in"))
      (node (ref "U12") (pin "28") (pinfunction "OUT_D_28") (pintype "power_in"))
    )
    (net (code "13") (name "Net-(C171-Pad1)") (class "Default")
      (node (ref "C171") (pin "1") (pinfunction "1_1") (pintype "passive"))
      (node (ref "C236") (pin "1") (pinfunction "1_1") (pintype "passive"))
      (node (ref "C510") (pin "1") (pinfunction "1_1") (pintype "passive"))
      (node (ref "C620") (pin "1") (pinfunction "1_1") (pintype "passive"))
      (node (ref "JWT1") (pin "1") (pinfunction "1_1") (pintype "passive"))
      (node (ref "JWT1") (pin "2") (pinfunction "2_2") (pintype "passive"))
      (node (ref "L23") (pin "2") (pinfunction "2_2") (pintype "passive"))
      (node (ref "TP103") (pin "1") (pinfunction "1_1") (pintype "passive"))
      (node (ref "TP43") (pin "1") (pinfunction "1_1") (pintype "passive"))
    )
    (net (code "14") (name "Net-(C171-Pad2)") (class "Default")
      (node (ref "C171") (pin "2") (pinfunction "2_2") (pintype "passive"))
      (node (ref "R225") (pin "2") (pinfunction "2_2") (pintype "passive"))
    )
    (net (code "15") (name "Net-(C177-Pad1)") (class "Default")
      (node (ref "C177") (pin "1") (pinfunction "1_1") (pintype "passive"))
      (node (ref "R229") (pin "1") (pinfunction "1_1") (pintype "passive"))
    )
    (net (code "16") (name "Net-(C177-Pad2)") (class "Default")
      (node (ref "C177") (pin "2") (pinfunction "2_2") (pintype "passive"))
      (node (ref "C246") (pin "2") (pinfunction "2_2") (pintype "passive"))
      (node (ref "C511") (pin "1") (pinfunction "1_1") (pintype "passive"))
      (node (ref "C621") (pin "2") (pinfunction "2_2") (pintype "passive"))
      (node (ref "JWT1") (pin "3") (pinfunction "3_3") (pintype "passive"))
      (node (ref "JWT1") (pin "4") (pinfunction "4_4") (pintype "passive"))
      (node (ref "L2") (pin "2") (pinfunction "2_2") (pintype "passive"))
      (node (ref "TP102") (pin "1") (pinfunction "1_1") (pintype "passive"))
      (node (ref "TP22") (pin "1") (pinfunction "1_1") (pintype "passive"))
    )
    (net (code "17") (name "Net-(C179-Pad2)") (class "Default")
      (node (ref "C179") (pin "2") (pinfunction "2_2") (pintype "passive"))
      (node (ref "L23") (pin "1") (pinfunction "1_1") (pintype "passive"))
      (node (ref "U12") (pin "39") (pinfunction "OUT_A_39") (pintype "power_in"))
      (node (ref "U12") (pin "40") (pinfunction "OUT_A_40") (pintype "power_in"))
    )
    (net (code "18") (name "Net-(C189-Pad1)") (class "Default")
      (node (ref "C189") (pin "1") (pinfunction "1_1") (pintype "passive"))
      (node (ref "C263") (pin "1") (pinfunction "1_1") (pintype "passive"))
      (node (ref "C5") (pin "1") (pinfunction "1_1") (pintype "passive"))
      (node (ref "C512") (pin "1") (pinfunction "1_1") (pintype "passive"))
      (node (ref "JWT1") (pin "5") (pinfunction "5_5") (pintype "passive"))
      (node (ref "L17") (pin "2") (pinfunction "2_2") (pintype "passive"))
      (node (ref "TP104") (pin "1") (pinfunction "1_1") (pintype "passive"))
      (node (ref "TP23") (pin "1") (pinfunction "1_1") (pintype "passive"))
    )
    (net (code "19") (name "Net-(C189-Pad2)") (class "Default")
      (node (ref "C189") (pin "2") (pinfunction "2_2") (pintype "passive"))
      (node (ref "R232") (pin "2") (pinfunction "2_2") (pintype "passive"))
    )
    (net (code "20") (name "Net-(C201-Pad1)") (class "Default")
      (node (ref "C201") (pin "1") (pinfunction "1_1") (pintype "passive"))
      (node (ref "R233") (pin "1") (pinfunction "1_1") (pintype "passive"))
    )
    (net (code "21") (name "Net-(C201-Pad2)") (class "Default")
      (node (ref "C201") (pin "2") (pinfunction "2_2") (pintype "passive"))
      (node (ref "C272") (pin "2") (pinfunction "2_2") (pintype "passive"))
      (node (ref "C5") (pin "2") (pinfunction "2_2") (pintype "passive"))
      (node (ref "C513") (pin "1") (pinfunction "1_1") (pintype "passive"))
      (node (ref "JWT1") (pin "6") (pinfunction "6_6") (pintype "passive"))
      (node (ref "L22") (pin "2") (pinfunction "2_2") (pintype "passive"))
      (node (ref "TP105") (pin "1") (pinfunction "1_1") (pintype "passive"))
      (node (ref "TP60") (pin "1") (pinfunction "1_1") (pintype "passive"))
    )
    (net (code "22") (name "Net-(U12-AVDD)") (class "Default")
      (node (ref "C256") (pin "2") (pinfunction "2_2") (pintype "passive"))
      (node (ref "C777") (pin "2") (pinfunction "2_2") (pintype "passive"))
      (node (ref "C778") (pin "2") (pinfunction "2_2") (pintype "passive"))
      (node (ref "U12") (pin "14") (pinfunction "AVDD_14") (pintype "power_in"))
    )
    (net (code "23") (name "Net-(U12-BST_A)") (class "Default")
      (node (ref "C179") (pin "1") (pinfunction "1_1") (pintype "passive"))
      (node (ref "U12") (pin "44") (pinfunction "BST_A_44") (pintype "power_in"))
    )
    (net (code "24") (name "Net-(U12-BST_B)") (class "Default")
      (node (ref "C12") (pin "1") (pinfunction "1_1") (pintype "passive"))
      (node (ref "U12") (pin "43") (pinfunction "BST_B_43") (pintype "power_in"))
    )
    (net (code "25") (name "Net-(U12-BST_C)") (class "Default")
      (node (ref "C190") (pin "2") (pinfunction "2_2") (pintype "passive"))
      (node (ref "U12") (pin "24") (pinfunction "BST_C_24") (pintype "power_in"))
    )
    (net (code "26") (name "Net-(U12-BST_D)") (class "Default")
      (node (ref "C13") (pin "2") (pinfunction "2_2") (pintype "passive"))
      (node (ref "U12") (pin "23") (pinfunction "BST_D_23") (pintype "power_in"))
    )
    (net (code "27") (name "Net-(U12-C_START)") (class "Default")
      (node (ref "C203") (pin "2") (pinfunction "2_2") (pintype "passive"))
      (node (ref "U12") (pin "15") (pinfunction "C_START_15") (pintype "output"))
    )
    (net (code "28") (name "Net-(U12-DVDD)") (class "Default")
      (node (ref "C254") (pin "2") (pinfunction "2_2") (pintype "passive"))
      (node (ref "C708") (pin "1") (pinfunction "1_1") (pintype "passive"))
      (node (ref "C709") (pin "1") (pinfunction "1_1") (pintype "passive"))
      (node (ref "U12") (pin "11") (pinfunction "DVDD_11") (pintype "power_in"))
    )
    (net (code "29") (name "Net-(U12-FREQ_ADJ)") (class "Default")
      (node (ref "R240") (pin "2") (pinfunction "2_2") (pintype "passive"))
      (node (ref "U12") (pin "8") (pinfunction "FREQ_ADJ_8") (pintype "input"))
    )
    (net (code "30") (name "Net-(U12-GVDD_AB)") (class "Default")
      (node (ref "C181") (pin "2") (pinfunction "2_2") (pintype "passive"))
      (node (ref "R261") (pin "2") (pinfunction "2_2") (pintype "passive"))
      (node (ref "U12") (pin "1") (pinfunction "GVDD_AB_1") (pintype "power_in"))
    )
    (net (code "31") (name "Net-(U12-GVDD_CD)") (class "Default")
      (node (ref "C185") (pin "2") (pinfunction "2_2") (pintype "passive"))
      (node (ref "R266") (pin "2") (pinfunction "2_2") (pintype "passive"))
      (node (ref "U12") (pin "22") (pinfunction "GVDD_CD_22") (pintype "power_in"))
    )
    (net (code "32") (name "Net-(U12-INPUT_A)") (class "Default")
      (node (ref "C180") (pin "1") (pinfunction "1_1") (pintype "passive"))
      (node (ref "R655") (pin "2") (pinfunction "2_2") (pintype "passive"))
      (node (ref "U12") (pin "5") (pinfunction "INPUT_A_5") (pintype "input"))
    )
    (net (code "33") (name "Net-(U12-INPUT_B)") (class "Default")
      (node (ref "C186") (pin "1") (pinfunction "1_1") (pintype "passive"))
      (node (ref "R655") (pin "1") (pinfunction "1_1") (pintype "passive"))
      (node (ref "U12") (pin "6") (pinfunction "INPUT_B_6") (pintype "input"))
    )
    (net (code "34") (name "Net-(U12-INPUT_C)") (class "Default")
      (node (ref "C187") (pin "1") (pinfunction "1_1") (pintype "passive"))
      (node (ref "R656") (pin "2") (pinfunction "2_2") (pintype "passive"))
      (node (ref "U12") (pin "16") (pinfunction "INPUT_C_16") (pintype "input"))
    )
    (net (code "35") (name "Net-(U12-INPUT_D)") (class "Default")
      (node (ref "C191") (pin "1") (pinfunction "1_1") (pintype "passive"))
      (node (ref "R656") (pin "1") (pinfunction "1_1") (pintype "passive"))
      (node (ref "U12") (pin "17") (pinfunction "INPUT_D_17") (pintype "input"))
    )
    (net (code "36") (name "Net-(U12-OC_ADJ)") (class "Default")
      (node (ref "R267") (pin "2") (pinfunction "2_2") (pintype "passive"))
      (node (ref "U12") (pin "7") (pinfunction "OC_ADJ_7") (pintype "input"))
    )
    (net (code "37") (name "Net-(U12-OUT_B)") (class "Default")
      (node (ref "C12") (pin "2") (pinfunction "2_2") (pintype "passive"))
      (node (ref "L2") (pin "1") (pinfunction "1_1") (pintype "passive"))
      (node (ref "U12") (pin "35") (pinfunction "OUT_B_35") (pintype "power_in"))
    )
    (net (code "38") (name "Net-(U12-OUT_C)") (class "Default")
      (node (ref "C190") (pin "1") (pinfunction "1_1") (pintype "passive"))
      (node (ref "L17") (pin "1") (pinfunction "1_1") (pintype "passive"))
      (node (ref "U12") (pin "32") (pinfunction "OUT_C_32") (pintype "power_in"))
    )
    (net (code "39") (name "Net-(U12-VBG)") (class "Default")
      (node (ref "C202") (pin "1") (pinfunction "1_1") (pintype "passive"))
      (node (ref "U12") (pin "20") (pinfunction "VBG_20") (pintype "passive"))
    )
    (net (code "40") (name "Net-(U20-Vin)") (class "Default")
      (node (ref "C23") (pin "1") (pinfunction "1_1") (pintype "passive"))
      (node (ref "C26") (pin "1") (pinfunction "1_1") (pintype "passive"))
      (node (ref "R680") (pin "2") (pinfunction "2_2") (pintype "passive"))
      (node (ref "U20") (pin "3") (pinfunction "Vin_3") (pintype "passive"))
    )
    (net (code "41") (name "unconnected-(U12-OC_IOM-Pad9)") (class "Default")
      (node (ref "U12") (pin "9") (pinfunction "OC_IOM_9") (pintype "bidirectional"))
    )
    (net (code "42") (name "unconnected-(U12-OC_IOP-Pad10)") (class "Default")
      (node (ref "U12") (pin "10") (pinfunction "OC_IOP_10") (pintype "bidirectional"))
    )
  )
)
